# HYDRA_V3_POWER.net
KiCad netlist of a schematic drawn in Altium Designer
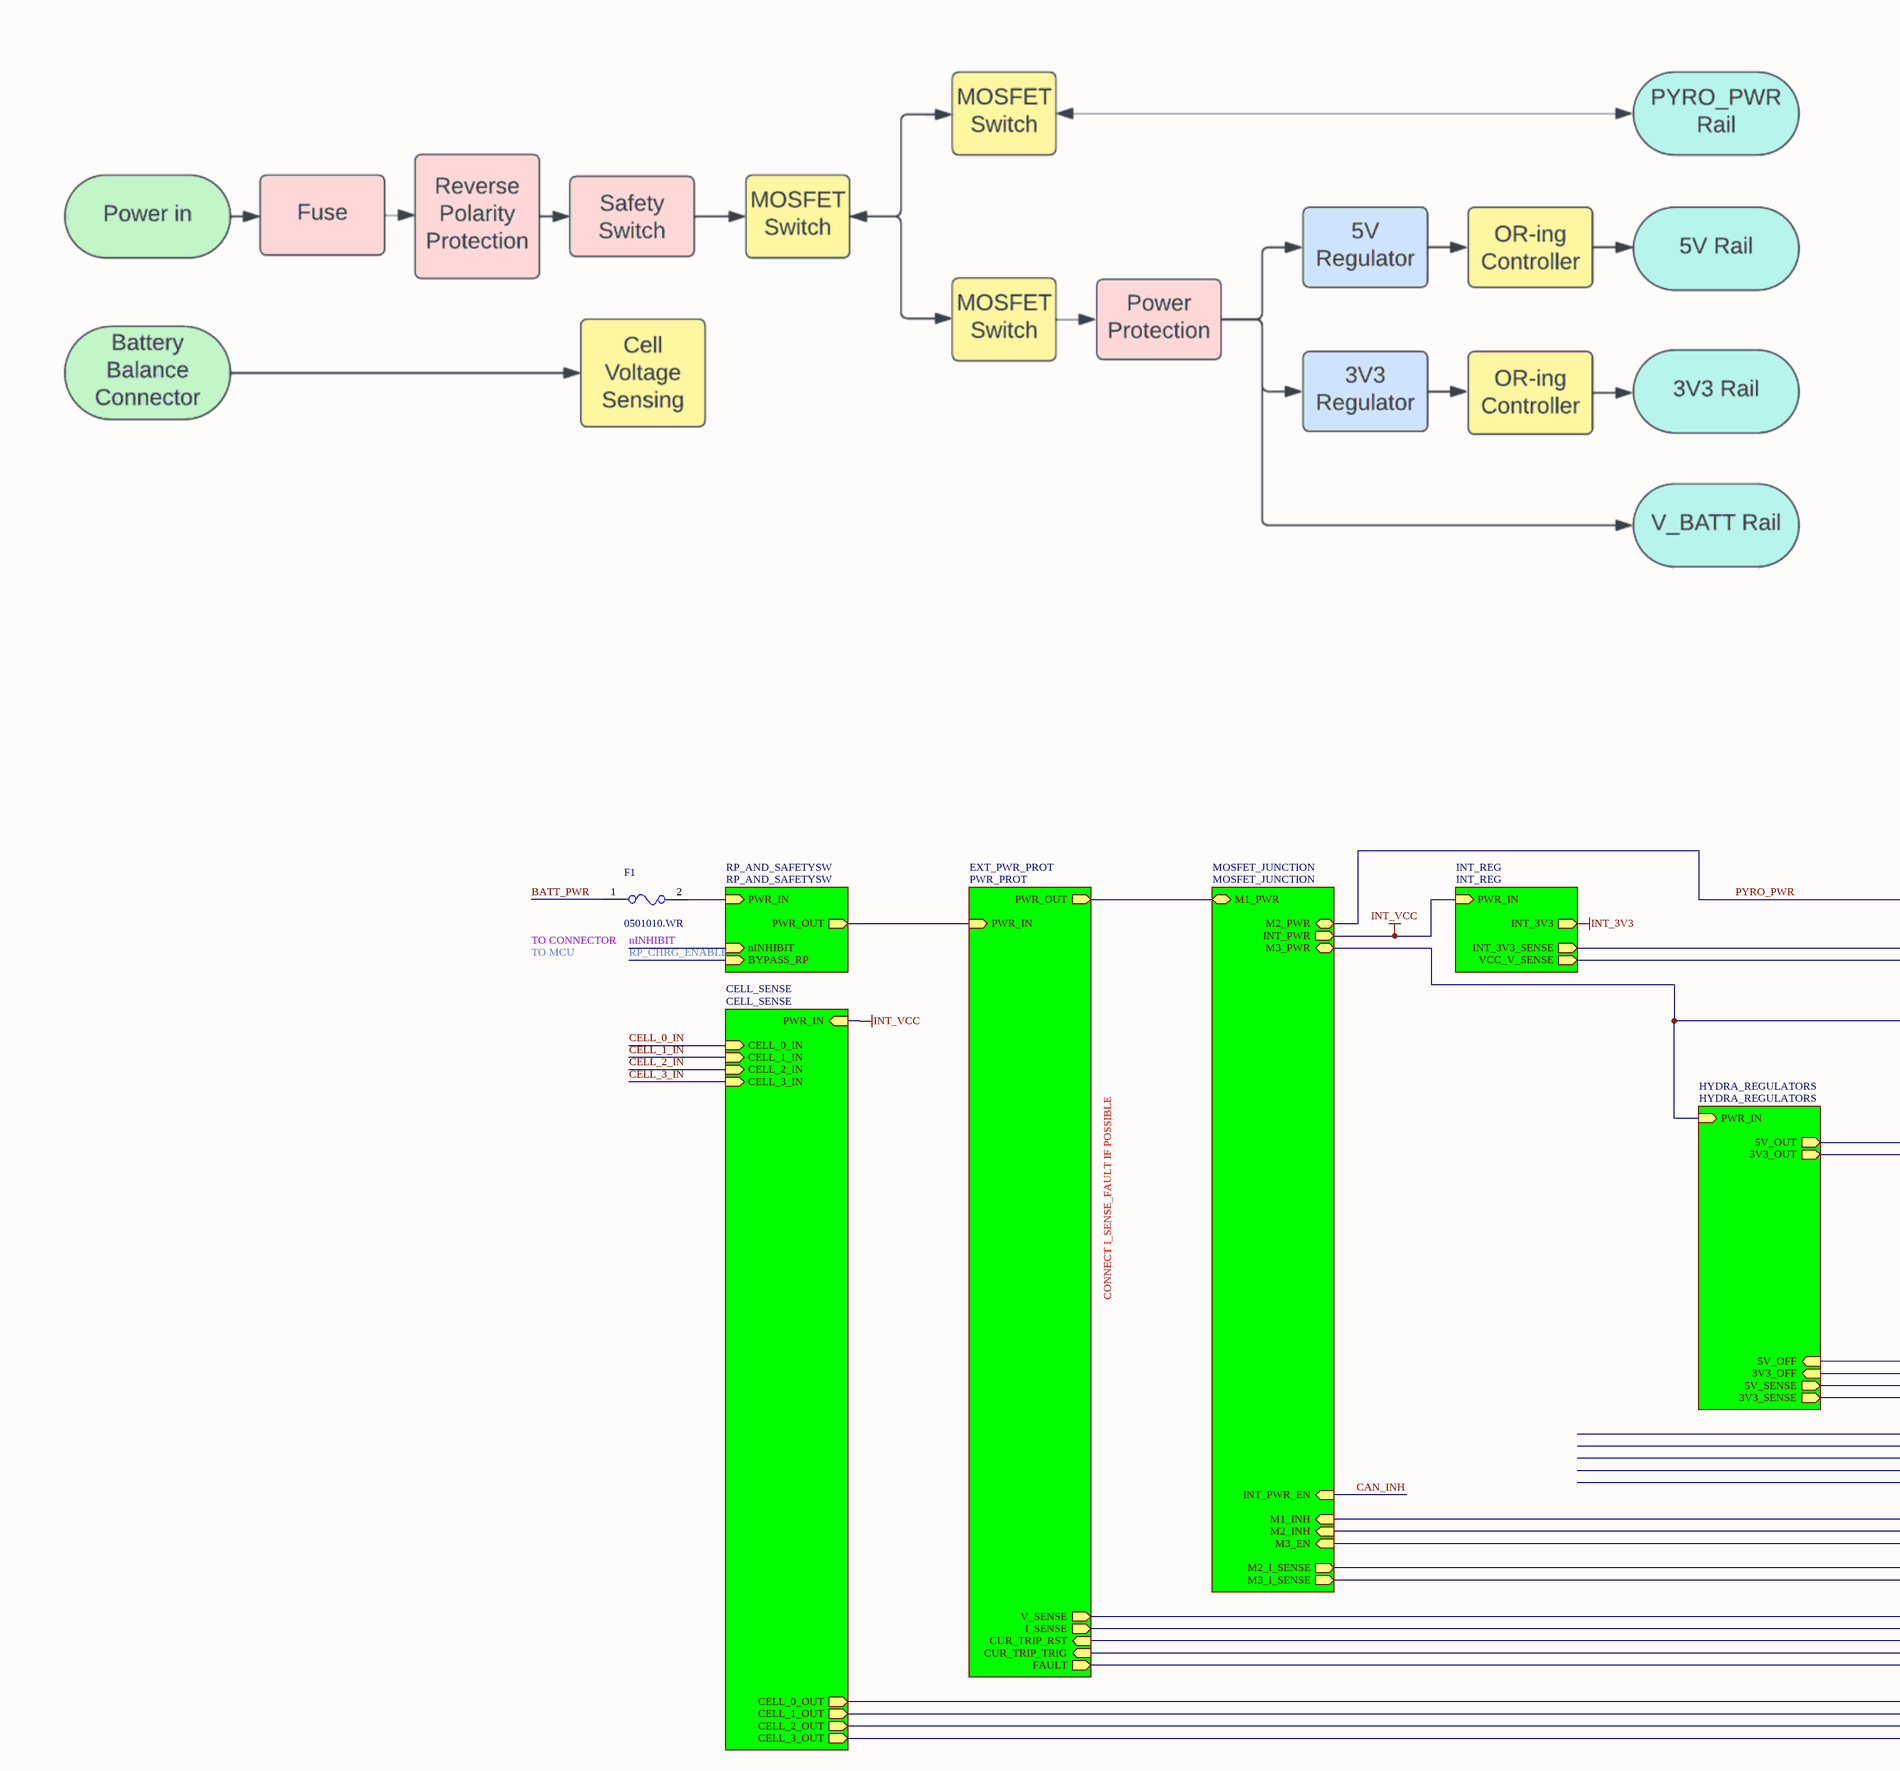
[diagram p0: HYDRA_V3_POWER.SchDoc, top left]
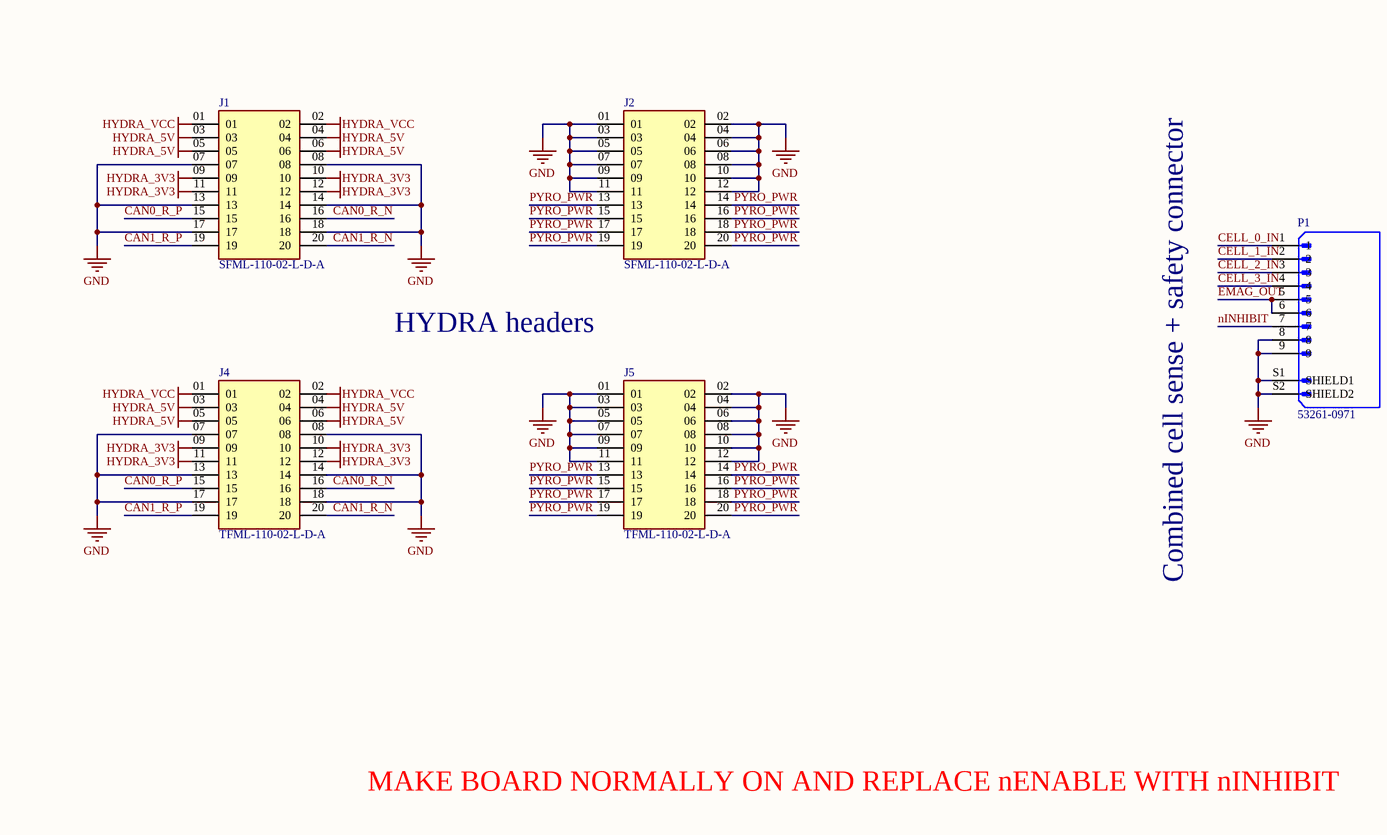
[diagram p1: HYDRA_V3_POWER.SchDoc, bottom left]
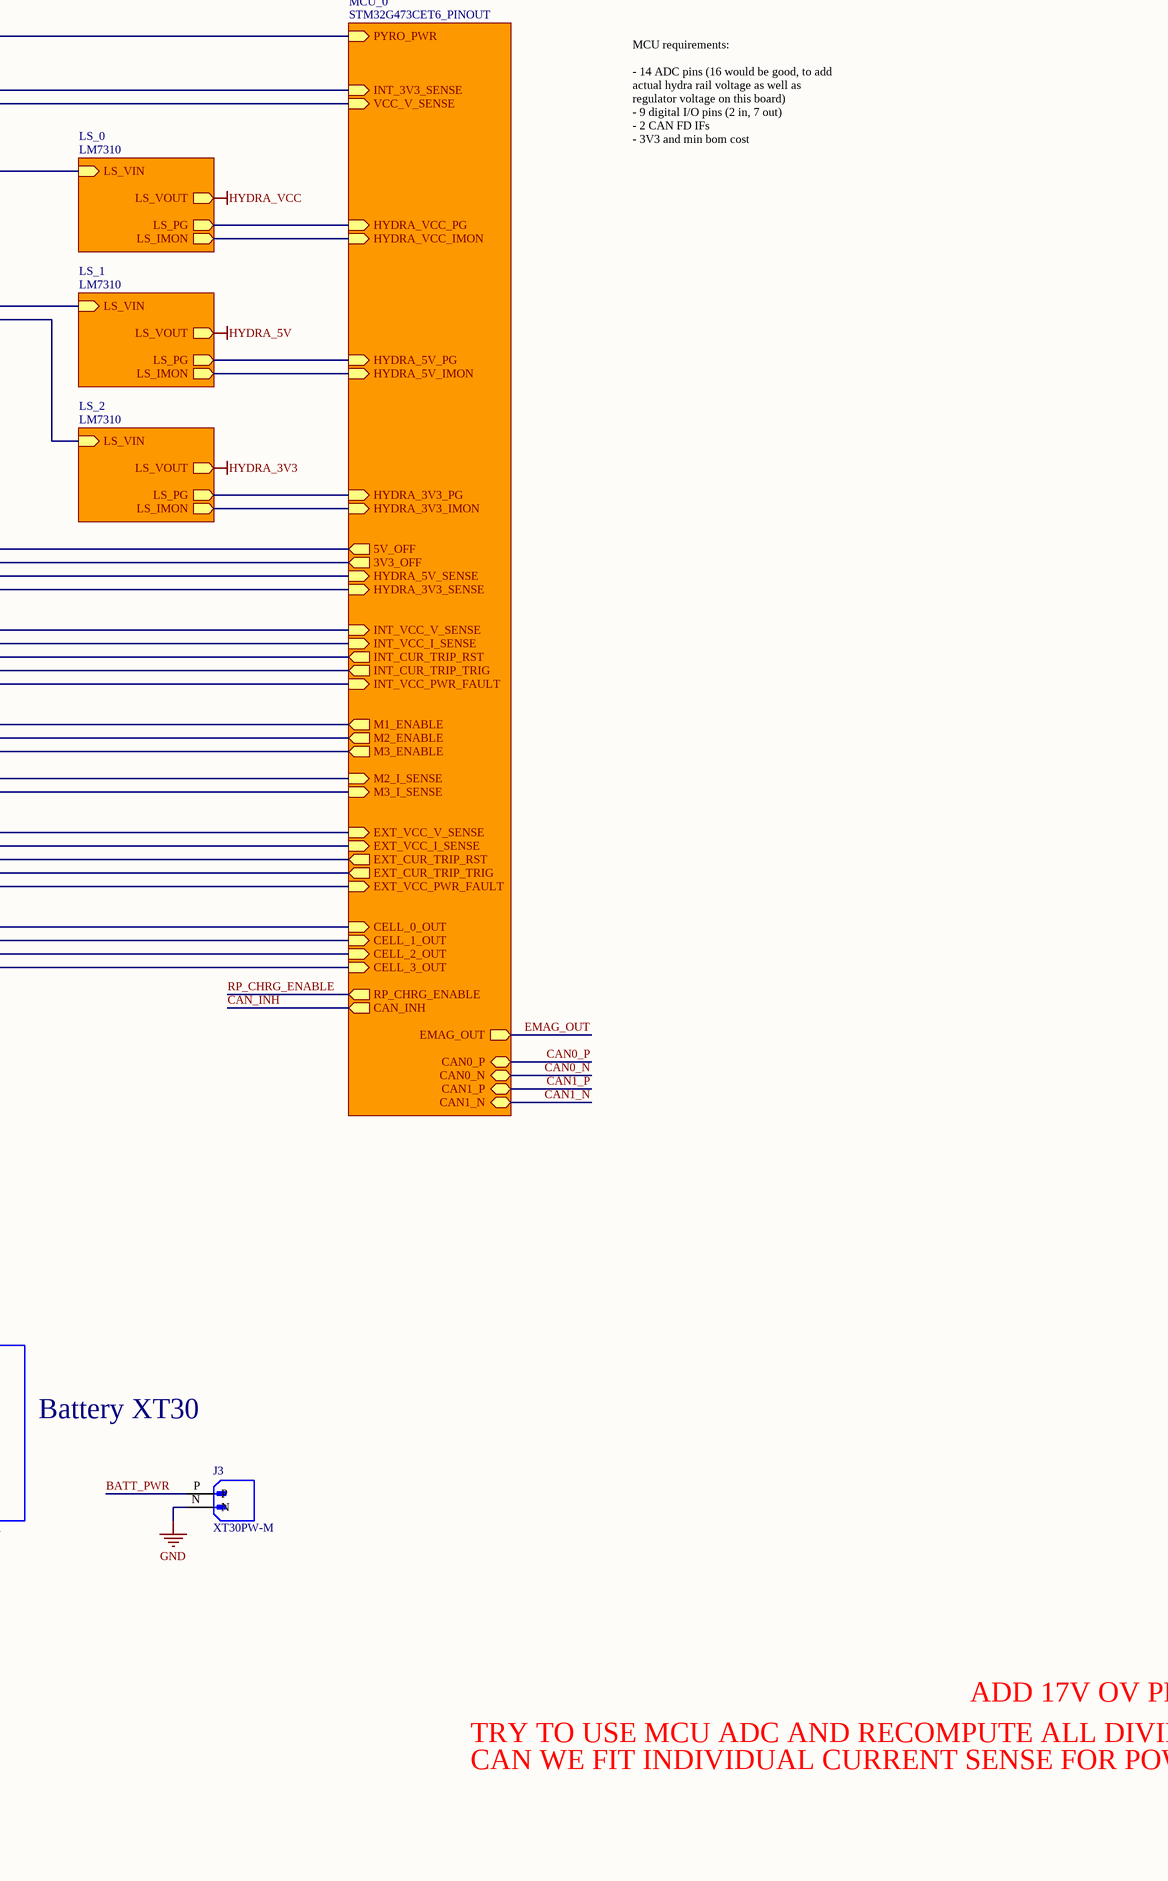
[diagram p2: HYDRA_V3_POWER.SchDoc, bottom right]

(export (version "E")
  (design (tool "Eeschema 10.0.6"))
  (components
    (comp (ref "F1")
      (value "0501010.WR")
      (footprint "FP-0501-MFG")
      (description "FUSE BOARD MOUNT 10A 32VDC 1206")
      (libsource (lib "Altium Content Vault") (part "5bcf9b9f640e542cf0359d10258e979"))
    )
    (comp (ref "J1")
      (value "SFML-110-02-L-D-A")
      (footprint "SFML-110-02-L-D-A-Footprint-1")
      (libsource (lib "Space Concordia") (part "SFML-110-02-L-D-A"))
    )
    (comp (ref "J2")
      (value "SFML-110-02-L-D-A")
      (footprint "SFML-110-02-L-D-A-Footprint-1")
      (libsource (lib "Space Concordia") (part "SFML-110-02-L-D-A"))
    )
    (comp (ref "J3")
      (value "XT30PW-M")
      (footprint "XT30PW-M-Footprint-1")
      (libsource (lib "Space Concordia") (part "XT30PW-M"))
    )
    (comp (ref "J4")
      (value "TFML-110-02-L-D-A")
      (footprint "TFML-110-02-L-D-A-Footprint-1")
      (description "Board Connector, 20 Contact(s), 2 Row(s), Male, Straight, Surface Mount Terminal")
      (libsource (lib "Space Concordia") (part "TFML-110-02-L-D-A"))
    )
    (comp (ref "J5")
      (value "TFML-110-02-L-D-A")
      (footprint "TFML-110-02-L-D-A-Footprint-1")
      (description "Board Connector, 20 Contact(s), 2 Row(s), Male, Straight, Surface Mount Terminal")
      (libsource (lib "Space Concordia") (part "TFML-110-02-L-D-A"))
    )
    (comp (ref "P1")
      (value "53261-0971")
      (footprint "53261-0971-Footprint-1")
      (libsource (lib "Space Concordia") (part "53261-0971"))
    )
  )
  (nets
    (net (code "7") (name "/BATT_PWR") (class "Default")
      (node (ref "F1") (pin "1") (pinfunction "1_1") (pintype "passive"))
      (node (ref "J3") (pin "P") (pinfunction "P_P") (pintype "power_in"))
    )
    (net (code "10") (name "/CAN0_R_N") (class "Default")
      (node (ref "J1") (pin "16") (pinfunction "16_16") (pintype "passive"))
      (node (ref "J4") (pin "16") (pinfunction "16_16") (pintype "passive"))
    )
    (net (code "11") (name "/CAN0_R_P") (class "Default")
      (node (ref "J1") (pin "15") (pinfunction "15_15") (pintype "passive"))
      (node (ref "J4") (pin "15") (pinfunction "15_15") (pintype "passive"))
    )
    (net (code "14") (name "/CAN1_R_N") (class "Default")
      (node (ref "J1") (pin "20") (pinfunction "20_20") (pintype "passive"))
      (node (ref "J4") (pin "20") (pinfunction "20_20") (pintype "passive"))
    )
    (net (code "15") (name "/CAN1_R_P") (class "Default")
      (node (ref "J1") (pin "19") (pinfunction "19_19") (pintype "passive"))
      (node (ref "J4") (pin "19") (pinfunction "19_19") (pintype "passive"))
    )
    (net (code "17") (name "/CELL_0_IN") (class "Default")
      (node (ref "P1") (pin "1") (pinfunction "1_1") (pintype "passive"))
    )
    (net (code "19") (name "/CELL_1_IN") (class "Default")
      (node (ref "P1") (pin "2") (pinfunction "2_2") (pintype "passive"))
    )
    (net (code "21") (name "/CELL_2_IN") (class "Default")
      (node (ref "P1") (pin "3") (pinfunction "3_3") (pintype "passive"))
    )
    (net (code "23") (name "/CELL_3_IN") (class "Default")
      (node (ref "P1") (pin "4") (pinfunction "4_4") (pintype "passive"))
    )
    (net (code "25") (name "/EMAG_OUT") (class "Default")
      (node (ref "P1") (pin "5") (pinfunction "5_5") (pintype "passive"))
      (node (ref "P1") (pin "6") (pinfunction "6_6") (pintype "passive"))
    )
    (net (code "48") (name "/PWR_IN") (class "Default")
      (node (ref "F1") (pin "2") (pinfunction "2_2") (pintype "passive"))
    )
    (net (code "51") (name "/PYRO_PWR") (class "Default")
      (node (ref "J2") (pin "13") (pinfunction "13_13") (pintype "passive"))
      (node (ref "J2") (pin "14") (pinfunction "14_14") (pintype "passive"))
      (node (ref "J2") (pin "15") (pinfunction "15_15") (pintype "passive"))
      (node (ref "J2") (pin "16") (pinfunction "16_16") (pintype "passive"))
      (node (ref "J2") (pin "17") (pinfunction "17_17") (pintype "passive"))
      (node (ref "J2") (pin "18") (pinfunction "18_18") (pintype "passive"))
      (node (ref "J2") (pin "19") (pinfunction "19_19") (pintype "passive"))
      (node (ref "J2") (pin "20") (pinfunction "20_20") (pintype "passive"))
      (node (ref "J5") (pin "13") (pinfunction "13_13") (pintype "passive"))
      (node (ref "J5") (pin "14") (pinfunction "14_14") (pintype "passive"))
      (node (ref "J5") (pin "15") (pinfunction "15_15") (pintype "passive"))
      (node (ref "J5") (pin "16") (pinfunction "16_16") (pintype "passive"))
      (node (ref "J5") (pin "17") (pinfunction "17_17") (pintype "passive"))
      (node (ref "J5") (pin "18") (pinfunction "18_18") (pintype "passive"))
      (node (ref "J5") (pin "19") (pinfunction "19_19") (pintype "passive"))
      (node (ref "J5") (pin "20") (pinfunction "20_20") (pintype "passive"))
    )
    (net (code "55") (name "/nINHIBIT") (class "Default")
      (node (ref "P1") (pin "7") (pinfunction "7_7") (pintype "passive"))
    )
    (net (code "56") (name "GND") (class "Default")
      (node (ref "J1") (pin "07") (pinfunction "07_07") (pintype "passive"))
      (node (ref "J1") (pin "08") (pinfunction "08_08") (pintype "passive"))
      (node (ref "J1") (pin "13") (pinfunction "13_13") (pintype "passive"))
      (node (ref "J1") (pin "14") (pinfunction "14_14") (pintype "passive"))
      (node (ref "J1") (pin "17") (pinfunction "17_17") (pintype "passive"))
      (node (ref "J1") (pin "18") (pinfunction "18_18") (pintype "passive"))
      (node (ref "J2") (pin "01") (pinfunction "01_01") (pintype "passive"))
      (node (ref "J2") (pin "02") (pinfunction "02_02") (pintype "passive"))
      (node (ref "J2") (pin "03") (pinfunction "03_03") (pintype "passive"))
      (node (ref "J2") (pin "04") (pinfunction "04_04") (pintype "passive"))
      (node (ref "J2") (pin "05") (pinfunction "05_05") (pintype "passive"))
      (node (ref "J2") (pin "06") (pinfunction "06_06") (pintype "passive"))
      (node (ref "J2") (pin "07") (pinfunction "07_07") (pintype "passive"))
      (node (ref "J2") (pin "08") (pinfunction "08_08") (pintype "passive"))
      (node (ref "J2") (pin "09") (pinfunction "09_09") (pintype "passive"))
      (node (ref "J2") (pin "10") (pinfunction "10_10") (pintype "passive"))
      (node (ref "J2") (pin "11") (pinfunction "11_11") (pintype "passive"))
      (node (ref "J2") (pin "12") (pinfunction "12_12") (pintype "passive"))
      (node (ref "J3") (pin "N") (pinfunction "N_N") (pintype "power_in"))
      (node (ref "J4") (pin "07") (pinfunction "07_07") (pintype "passive"))
      (node (ref "J4") (pin "08") (pinfunction "08_08") (pintype "passive"))
      (node (ref "J4") (pin "13") (pinfunction "13_13") (pintype "passive"))
      (node (ref "J4") (pin "14") (pinfunction "14_14") (pintype "passive"))
      (node (ref "J4") (pin "17") (pinfunction "17_17") (pintype "passive"))
      (node (ref "J4") (pin "18") (pinfunction "18_18") (pintype "passive"))
      (node (ref "J5") (pin "01") (pinfunction "01_01") (pintype "passive"))
      (node (ref "J5") (pin "02") (pinfunction "02_02") (pintype "passive"))
      (node (ref "J5") (pin "03") (pinfunction "03_03") (pintype "passive"))
      (node (ref "J5") (pin "04") (pinfunction "04_04") (pintype "passive"))
      (node (ref "J5") (pin "05") (pinfunction "05_05") (pintype "passive"))
      (node (ref "J5") (pin "06") (pinfunction "06_06") (pintype "passive"))
      (node (ref "J5") (pin "07") (pinfunction "07_07") (pintype "passive"))
      (node (ref "J5") (pin "08") (pinfunction "08_08") (pintype "passive"))
      (node (ref "J5") (pin "09") (pinfunction "09_09") (pintype "passive"))
      (node (ref "J5") (pin "10") (pinfunction "10_10") (pintype "passive"))
      (node (ref "J5") (pin "11") (pinfunction "11_11") (pintype "passive"))
      (node (ref "J5") (pin "12") (pinfunction "12_12") (pintype "passive"))
      (node (ref "P1") (pin "8") (pinfunction "8_8") (pintype "passive"))
      (node (ref "P1") (pin "9") (pinfunction "9_9") (pintype "passive"))
      (node (ref "P1") (pin "S1") (pinfunction "SHIELD1_S1") (pintype "passive"))
      (node (ref "P1") (pin "S2") (pinfunction "SHIELD2_S2") (pintype "passive"))
    )
    (net (code "57") (name "HYDRA_3V3") (class "Default")
      (node (ref "J1") (pin "09") (pinfunction "09_09") (pintype "passive"))
      (node (ref "J1") (pin "10") (pinfunction "10_10") (pintype "passive"))
      (node (ref "J1") (pin "11") (pinfunction "11_11") (pintype "passive"))
      (node (ref "J1") (pin "12") (pinfunction "12_12") (pintype "passive"))
      (node (ref "J4") (pin "09") (pinfunction "09_09") (pintype "passive"))
      (node (ref "J4") (pin "10") (pinfunction "10_10") (pintype "passive"))
      (node (ref "J4") (pin "11") (pinfunction "11_11") (pintype "passive"))
      (node (ref "J4") (pin "12") (pinfunction "12_12") (pintype "passive"))
    )
    (net (code "58") (name "HYDRA_5V") (class "Default")
      (node (ref "J1") (pin "03") (pinfunction "03_03") (pintype "passive"))
      (node (ref "J1") (pin "04") (pinfunction "04_04") (pintype "passive"))
      (node (ref "J1") (pin "05") (pinfunction "05_05") (pintype "passive"))
      (node (ref "J1") (pin "06") (pinfunction "06_06") (pintype "passive"))
      (node (ref "J4") (pin "03") (pinfunction "03_03") (pintype "passive"))
      (node (ref "J4") (pin "04") (pinfunction "04_04") (pintype "passive"))
      (node (ref "J4") (pin "05") (pinfunction "05_05") (pintype "passive"))
      (node (ref "J4") (pin "06") (pinfunction "06_06") (pintype "passive"))
    )
    (net (code "59") (name "HYDRA_VCC") (class "Default")
      (node (ref "J1") (pin "01") (pinfunction "01_01") (pintype "passive"))
      (node (ref "J1") (pin "02") (pinfunction "02_02") (pintype "passive"))
      (node (ref "J4") (pin "01") (pinfunction "01_01") (pintype "passive"))
      (node (ref "J4") (pin "02") (pinfunction "02_02") (pintype "passive"))
    )
  )
)
